# 05_FMC_HPC1.net
KiCad netlist of a schematic drawn in Altium Designer
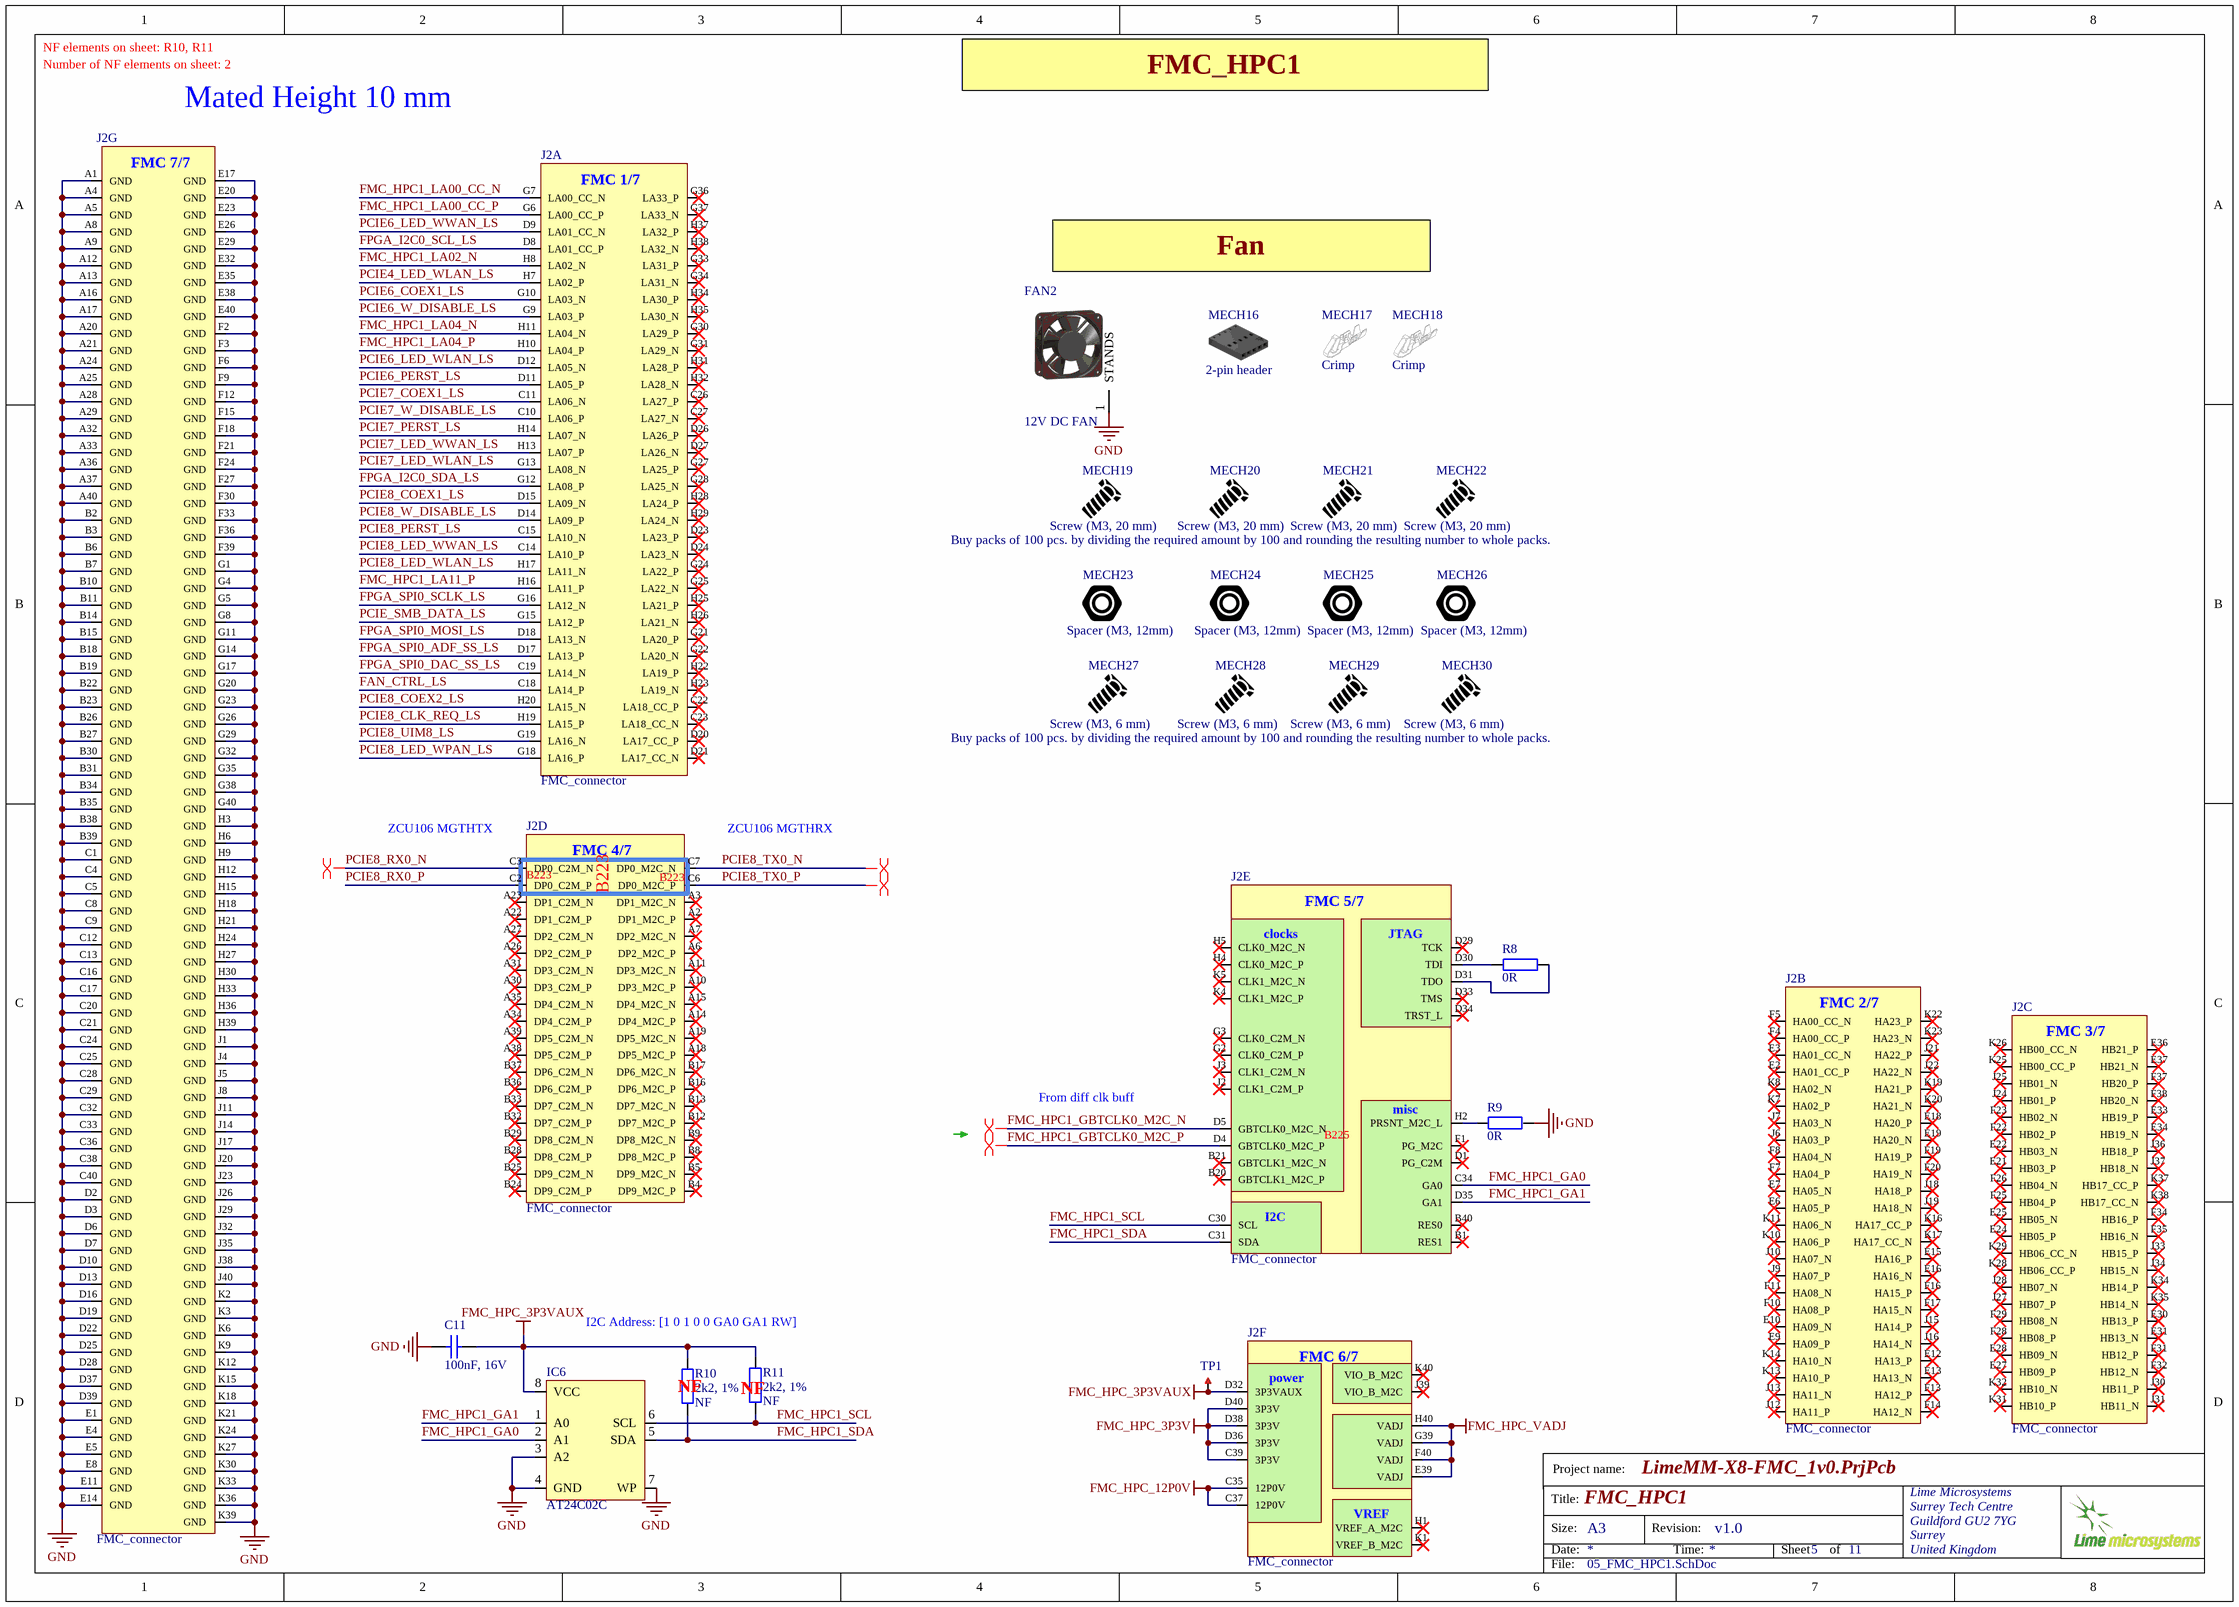
[diagram p0: 05_FMC_HPC1.SchDoc]

(export (version "E")
  (design (tool "Eeschema 10.0.6"))
  (components
    (comp (ref "C11")
      (value "100nF, 16V")
      (footprint "CAP0402")
      (fields (field (name "TOLERANCE") "10 %") (field (name "MANUFACTURER") "Murata Electronics"))
      (libsource (lib "LimeFPGAboard_schLib") (part "Cap_0603"))
    )
    (comp (ref "FAN2")
      (value "12V DC FAN")
      (footprint "FAN_80mm")
      (fields (field (name "MANUFACTURER") "Sunon"))
      (libsource (lib "LimeMicroAltiumLib_schLib_r04") (part "12V_DC_FAN"))
    )
    (comp (ref "IC6")
      (value "AT24C02C")
      (footprint "SOIC127P600-8DL_v2")
      (fields (field (name "MANUFACTURER") "ATMEL"))
      (libsource (lib "LimeMicroAltiumLib_schLib") (part "AT24C02C-SSHM-B"))
    )
    (comp (ref "J2")
      (value "FMC_connector")
      (footprint "FMC_HPC_terminal_conn_ASP-134488-01")
      (fields (field (name "MANUFACTURER") "Samtec"))
      (libsource (lib "LimeMicroAltiumLib") (part "FMC_connector"))
    )
    (comp (ref "MECH16")
      (value "2-pin header")
      (fields (field (name "MANUFACTURER") "Molex"))
      (libsource (lib "LimeMicroAltiumLib_schLib_r05") (part "Universal_crimped_header"))
    )
    (comp (ref "MECH17")
      (value "Crimp")
      (fields (field (name "MANUFACTURER") "Molex"))
      (libsource (lib "LimeMicroAltiumLib_schLib_r05") (part "Universal_crimp"))
    )
    (comp (ref "MECH18")
      (value "Crimp")
      (fields (field (name "MANUFACTURER") "Molex"))
      (libsource (lib "LimeMicroAltiumLib_schLib_r05") (part "Universal_crimp"))
    )
    (comp (ref "MECH19")
      (value "Screw (M3, 20 mm)")
      (fields (field (name "MANUFACTURER") "TR Fastenings"))
      (libsource (lib "LimeMicroAltiumLib_schLib_r05") (part "Universal_mech_screw"))
    )
    (comp (ref "MECH20")
      (value "Screw (M3, 20 mm)")
      (fields
        (field (name "ASSEMBLY INFO") "Buy packs of 100 pcs. by dividing the required amount by 100 and rounding the resulting number to whole packs.")
        (field (name "MANUFACTURER") "TR Fastenings")
      )
      (libsource (lib "LimeMicroAltiumLib_schLib_r05") (part "Universal_mech_screw"))
    )
    (comp (ref "MECH21")
      (value "Screw (M3, 20 mm)")
      (fields (field (name "MANUFACTURER") "TR Fastenings"))
      (libsource (lib "LimeMicroAltiumLib_schLib_r05") (part "Universal_mech_screw"))
    )
    (comp (ref "MECH22")
      (value "Screw (M3, 20 mm)")
      (fields (field (name "MANUFACTURER") "TR Fastenings"))
      (libsource (lib "LimeMicroAltiumLib_schLib_r05") (part "Universal_mech_screw"))
    )
    (comp (ref "MECH23")
      (value "Spacer (M3, 12mm)")
      (fields (field (name "MANUFACTURER") "ETTINGER"))
      (libsource (lib "LimeMicroAltiumLib_schLib_r05") (part "Universal_mech_nut"))
    )
    (comp (ref "MECH24")
      (value "Spacer (M3, 12mm)")
      (fields (field (name "MANUFACTURER") "ETTINGER"))
      (libsource (lib "LimeMicroAltiumLib_schLib_r05") (part "Universal_mech_nut"))
    )
    (comp (ref "MECH25")
      (value "Spacer (M3, 12mm)")
      (fields (field (name "MANUFACTURER") "ETTINGER"))
      (libsource (lib "LimeMicroAltiumLib_schLib_r05") (part "Universal_mech_nut"))
    )
    (comp (ref "MECH26")
      (value "Spacer (M3, 12mm)")
      (fields (field (name "MANUFACTURER") "ETTINGER"))
      (libsource (lib "LimeMicroAltiumLib_schLib_r05") (part "Universal_mech_nut"))
    )
    (comp (ref "MECH27")
      (value "Screw (M3, 6 mm)")
      (fields (field (name "MANUFACTURER") "TR Fastenings"))
      (libsource (lib "LimeMicroAltiumLib_schLib_r05") (part "Universal_mech_screw"))
    )
    (comp (ref "MECH28")
      (value "Screw (M3, 6 mm)")
      (fields
        (field (name "ASSEMBLY INFO") "Buy packs of 100 pcs. by dividing the required amount by 100 and rounding the resulting number to whole packs.")
        (field (name "MANUFACTURER") "TR Fastenings")
      )
      (libsource (lib "LimeMicroAltiumLib_schLib_r05") (part "Universal_mech_screw"))
    )
    (comp (ref "MECH29")
      (value "Screw (M3, 6 mm)")
      (fields (field (name "MANUFACTURER") "TR Fastenings"))
      (libsource (lib "LimeMicroAltiumLib_schLib_r05") (part "Universal_mech_screw"))
    )
    (comp (ref "MECH30")
      (value "Screw (M3, 6 mm)")
      (fields (field (name "MANUFACTURER") "TR Fastenings"))
      (libsource (lib "LimeMicroAltiumLib_schLib_r05") (part "Universal_mech_screw"))
    )
    (comp (ref "R8")
      (value "0R")
      (footprint "RES0402")
      (fields (field (name "MANUFACTURER") "Yageo") (field (name "TOLERANCE") "Jumper"))
      (libsource (lib "") (part "Res_0402_1"))
    )
    (comp (ref "R9")
      (value "0R")
      (footprint "RES0402")
      (fields (field (name "MANUFACTURER") "Yageo") (field (name "TOLERANCE") "Jumper"))
      (libsource (lib "LimeMicroAltiumLib_schLib") (part "Res_0402"))
    )
    (comp (ref "R10")
      (value "2k2, 1%")
      (footprint "RES0402")
      (fields
        (field (name "ASSEMBLY INFO") "NF")
        (field (name "MANUFACTURER") "Stackpole Electronics Inc")
        (field (name "TOLERANCE") "±1%")
      )
      (libsource (lib "") (part "Res_0402_1"))
    )
    (comp (ref "R11")
      (value "2k2, 1%")
      (footprint "RES0402")
      (fields
        (field (name "ASSEMBLY INFO") "NF")
        (field (name "MANUFACTURER") "Stackpole Electronics Inc")
        (field (name "TOLERANCE") "±1%")
      )
      (libsource (lib "") (part "Res_0402_1"))
    )
    (comp (ref "TP1")
      (value "TESTPOINT_PAD")
      (footprint "TP_PAD_1p5MM")
      (description "Test Point PCB mount Miniature White")
      (libsource (lib "LimeMicroAltiumLib_schLib_r04") (part "TESTPOINT_PAD"))
    )
  )
  (nets
    (net (code "1") (name "/FAN_CTRL_LS") (class "Default")
      (node (ref "J2") (pin "C18") (pinfunction "LA14_P_C18") (pintype "passive"))
    )
    (net (code "2") (name "/FMC_HPC1_GA0") (class "Default")
      (node (ref "IC6") (pin "2") (pinfunction "A1_2") (pintype "passive"))
      (node (ref "J2") (pin "C34") (pinfunction "GA0_C34") (pintype "passive"))
    )
    (net (code "3") (name "/FMC_HPC1_GA1") (class "Default")
      (node (ref "IC6") (pin "1") (pinfunction "A0_1") (pintype "passive"))
      (node (ref "J2") (pin "D35") (pinfunction "GA1_D35") (pintype "passive"))
    )
    (net (code "4") (name "/FMC_HPC1_GBTCLK0_M2C_N") (class "Default")
      (node (ref "J2") (pin "D5") (pinfunction "GBTCLK0_M2C_N_D5") (pintype "passive"))
    )
    (net (code "5") (name "/FMC_HPC1_GBTCLK0_M2C_P") (class "Default")
      (node (ref "J2") (pin "D4") (pinfunction "GBTCLK0_M2C_P_D4") (pintype "passive"))
    )
    (net (code "6") (name "/FMC_HPC1_LA00_CC_N") (class "Default")
      (node (ref "J2") (pin "G7") (pinfunction "LA00_CC_N_G7") (pintype "passive"))
    )
    (net (code "7") (name "/FMC_HPC1_LA00_CC_P") (class "Default")
      (node (ref "J2") (pin "G6") (pinfunction "LA00_CC_P_G6") (pintype "passive"))
    )
    (net (code "8") (name "/FMC_HPC1_LA02_N") (class "Default")
      (node (ref "J2") (pin "H8") (pinfunction "LA02_N_H8") (pintype "passive"))
    )
    (net (code "9") (name "/FMC_HPC1_LA04_N") (class "Default")
      (node (ref "J2") (pin "H11") (pinfunction "LA04_N_H11") (pintype "passive"))
    )
    (net (code "10") (name "/FMC_HPC1_LA04_P") (class "Default")
      (node (ref "J2") (pin "H10") (pinfunction "LA04_P_H10") (pintype "passive"))
    )
    (net (code "11") (name "/FMC_HPC1_LA11_P") (class "Default")
      (node (ref "J2") (pin "H16") (pinfunction "LA11_P_H16") (pintype "passive"))
    )
    (net (code "12") (name "/FMC_HPC1_SCL") (class "Default")
      (node (ref "IC6") (pin "6") (pinfunction "SCL_6") (pintype "passive"))
      (node (ref "J2") (pin "C30") (pinfunction "SCL_C30") (pintype "passive"))
      (node (ref "R11") (pin "2") (pinfunction "2_2") (pintype "passive"))
    )
    (net (code "13") (name "/FMC_HPC1_SDA") (class "Default")
      (node (ref "IC6") (pin "5") (pinfunction "SDA_5") (pintype "passive"))
      (node (ref "J2") (pin "C31") (pinfunction "SDA_C31") (pintype "passive"))
      (node (ref "R10") (pin "2") (pinfunction "2_2") (pintype "passive"))
    )
    (net (code "14") (name "/FPGA_I2C0_SCL_LS") (class "Default")
      (node (ref "J2") (pin "D8") (pinfunction "LA01_CC_P_D8") (pintype "passive"))
    )
    (net (code "15") (name "/FPGA_I2C0_SDA_LS") (class "Default")
      (node (ref "J2") (pin "G12") (pinfunction "LA08_P_G12") (pintype "passive"))
    )
    (net (code "16") (name "/FPGA_SPI0_ADF_SS_LS") (class "Default")
      (node (ref "J2") (pin "D17") (pinfunction "LA13_P_D17") (pintype "passive"))
    )
    (net (code "17") (name "/FPGA_SPI0_DAC_SS_LS") (class "Default")
      (node (ref "J2") (pin "C19") (pinfunction "LA14_N_C19") (pintype "passive"))
    )
    (net (code "18") (name "/FPGA_SPI0_MOSI_LS") (class "Default")
      (node (ref "J2") (pin "D18") (pinfunction "LA13_N_D18") (pintype "passive"))
    )
    (net (code "19") (name "/FPGA_SPI0_SCLK_LS") (class "Default")
      (node (ref "J2") (pin "G16") (pinfunction "LA12_N_G16") (pintype "passive"))
    )
    (net (code "20") (name "/PCIE4_LED_WLAN_LS") (class "Default")
      (node (ref "J2") (pin "H7") (pinfunction "LA02_P_H7") (pintype "passive"))
    )
    (net (code "21") (name "/PCIE6_COEX1_LS") (class "Default")
      (node (ref "J2") (pin "G10") (pinfunction "LA03_N_G10") (pintype "passive"))
    )
    (net (code "22") (name "/PCIE6_LED_WLAN_LS") (class "Default")
      (node (ref "J2") (pin "D12") (pinfunction "LA05_N_D12") (pintype "passive"))
    )
    (net (code "23") (name "/PCIE6_LED_WWAN_LS") (class "Default")
      (node (ref "J2") (pin "D9") (pinfunction "LA01_CC_N_D9") (pintype "passive"))
    )
    (net (code "24") (name "/PCIE6_PERST_LS") (class "Default")
      (node (ref "J2") (pin "D11") (pinfunction "LA05_P_D11") (pintype "passive"))
    )
    (net (code "25") (name "/PCIE6_W_DISABLE_LS") (class "Default")
      (node (ref "J2") (pin "G9") (pinfunction "LA03_P_G9") (pintype "passive"))
    )
    (net (code "26") (name "/PCIE7_COEX1_LS") (class "Default")
      (node (ref "J2") (pin "C11") (pinfunction "LA06_N_C11") (pintype "passive"))
    )
    (net (code "27") (name "/PCIE7_LED_WLAN_LS") (class "Default")
      (node (ref "J2") (pin "G13") (pinfunction "LA08_N_G13") (pintype "passive"))
    )
    (net (code "28") (name "/PCIE7_LED_WWAN_LS") (class "Default")
      (node (ref "J2") (pin "H13") (pinfunction "LA07_P_H13") (pintype "passive"))
    )
    (net (code "29") (name "/PCIE7_PERST_LS") (class "Default")
      (node (ref "J2") (pin "H14") (pinfunction "LA07_N_H14") (pintype "passive"))
    )
    (net (code "30") (name "/PCIE7_W_DISABLE_LS") (class "Default")
      (node (ref "J2") (pin "C10") (pinfunction "LA06_P_C10") (pintype "passive"))
    )
    (net (code "31") (name "/PCIE8_CLK_REQ_LS") (class "Default")
      (node (ref "J2") (pin "H19") (pinfunction "LA15_P_H19") (pintype "passive"))
    )
    (net (code "32") (name "/PCIE8_COEX1_LS") (class "Default")
      (node (ref "J2") (pin "D15") (pinfunction "LA09_N_D15") (pintype "passive"))
    )
    (net (code "33") (name "/PCIE8_COEX2_LS") (class "Default")
      (node (ref "J2") (pin "H20") (pinfunction "LA15_N_H20") (pintype "passive"))
    )
    (net (code "34") (name "/PCIE8_LED_WLAN_LS") (class "Default")
      (node (ref "J2") (pin "H17") (pinfunction "LA11_N_H17") (pintype "passive"))
    )
    (net (code "35") (name "/PCIE8_LED_WPAN_LS") (class "Default")
      (node (ref "J2") (pin "G18") (pinfunction "LA16_P_G18") (pintype "passive"))
    )
    (net (code "36") (name "/PCIE8_LED_WWAN_LS") (class "Default")
      (node (ref "J2") (pin "C14") (pinfunction "LA10_P_C14") (pintype "passive"))
    )
    (net (code "37") (name "/PCIE8_PERST_LS") (class "Default")
      (node (ref "J2") (pin "C15") (pinfunction "LA10_N_C15") (pintype "passive"))
    )
    (net (code "38") (name "/PCIE8_RX0_N") (class "Default")
      (node (ref "J2") (pin "C3") (pinfunction "DP0_C2M_N_C3") (pintype "passive"))
    )
    (net (code "39") (name "/PCIE8_RX0_P") (class "Default")
      (node (ref "J2") (pin "C2") (pinfunction "DP0_C2M_P_C2") (pintype "passive"))
    )
    (net (code "40") (name "/PCIE8_TX0_N") (class "Default")
      (node (ref "J2") (pin "C7") (pinfunction "DP0_M2C_N_C7") (pintype "passive"))
    )
    (net (code "41") (name "/PCIE8_TX0_P") (class "Default")
      (node (ref "J2") (pin "C6") (pinfunction "DP0_M2C_P_C6") (pintype "passive"))
    )
    (net (code "42") (name "/PCIE8_UIM8_LS") (class "Default")
      (node (ref "J2") (pin "G19") (pinfunction "LA16_N_G19") (pintype "passive"))
    )
    (net (code "43") (name "/PCIE8_W_DISABLE_LS") (class "Default")
      (node (ref "J2") (pin "D14") (pinfunction "LA09_P_D14") (pintype "passive"))
    )
    (net (code "44") (name "/PCIE_SMB_DATA_LS") (class "Default")
      (node (ref "J2") (pin "G15") (pinfunction "LA12_P_G15") (pintype "passive"))
    )
    (net (code "45") (name "FMC_HPC_3P3V") (class "Default")
      (node (ref "J2") (pin "C39") (pinfunction "3P3V_C39") (pintype "passive"))
      (node (ref "J2") (pin "D36") (pinfunction "3P3V_D36") (pintype "passive"))
      (node (ref "J2") (pin "D38") (pinfunction "3P3V_D38") (pintype "passive"))
      (node (ref "J2") (pin "D40") (pinfunction "3P3V_D40") (pintype "passive"))
    )
    (net (code "46") (name "FMC_HPC_3P3VAUX") (class "Default")
      (node (ref "C11") (pin "1") (pinfunction "1_1") (pintype "passive"))
      (node (ref "IC6") (pin "8") (pinfunction "VCC_8") (pintype "passive"))
      (node (ref "J2") (pin "D32") (pinfunction "3P3VAUX_D32") (pintype "passive"))
      (node (ref "R10") (pin "1") (pinfunction "1_1") (pintype "passive"))
      (node (ref "R11") (pin "1") (pinfunction "1_1") (pintype "passive"))
      (node (ref "TP1") (pin "1") (pintype "passive"))
    )
    (net (code "47") (name "FMC_HPC_12P0V") (class "Default")
      (node (ref "J2") (pin "C35") (pinfunction "12P0V_C35") (pintype "passive"))
      (node (ref "J2") (pin "C37") (pinfunction "12P0V_C37") (pintype "passive"))
    )
    (net (code "48") (name "FMC_HPC_VADJ") (class "Default")
      (node (ref "J2") (pin "E39") (pinfunction "VADJ_E39") (pintype "passive"))
      (node (ref "J2") (pin "F40") (pinfunction "VADJ_F40") (pintype "passive"))
      (node (ref "J2") (pin "G39") (pinfunction "VADJ_G39") (pintype "passive"))
      (node (ref "J2") (pin "H40") (pinfunction "VADJ_H40") (pintype "passive"))
    )
    (net (code "49") (name "GND") (class "Default")
      (node (ref "C11") (pin "2") (pinfunction "2_2") (pintype "passive"))
      (node (ref "FAN2") (pin "1") (pinfunction "STANDS_1") (pintype "passive"))
      (node (ref "IC6") (pin "3") (pinfunction "A2_3") (pintype "passive"))
      (node (ref "IC6") (pin "4") (pinfunction "GND_4") (pintype "passive"))
      (node (ref "IC6") (pin "7") (pinfunction "WP_7") (pintype "passive"))
      (node (ref "J2") (pin "A1") (pinfunction "GND_A1") (pintype "passive"))
      (node (ref "J2") (pin "A12") (pinfunction "GND_A12") (pintype "passive"))
      (node (ref "J2") (pin "A13") (pinfunction "GND_A13") (pintype "passive"))
      (node (ref "J2") (pin "A16") (pinfunction "GND_A16") (pintype "passive"))
      (node (ref "J2") (pin "A17") (pinfunction "GND_A17") (pintype "passive"))
      (node (ref "J2") (pin "A20") (pinfunction "GND_A20") (pintype "passive"))
      (node (ref "J2") (pin "A21") (pinfunction "GND_A21") (pintype "passive"))
      (node (ref "J2") (pin "A24") (pinfunction "GND_A24") (pintype "passive"))
      (node (ref "J2") (pin "A25") (pinfunction "GND_A25") (pintype "passive"))
      (node (ref "J2") (pin "A28") (pinfunction "GND_A28") (pintype "passive"))
      (node (ref "J2") (pin "A29") (pinfunction "GND_A29") (pintype "passive"))
      (node (ref "J2") (pin "A32") (pinfunction "GND_A32") (pintype "passive"))
      (node (ref "J2") (pin "A33") (pinfunction "GND_A33") (pintype "passive"))
      (node (ref "J2") (pin "A36") (pinfunction "GND_A36") (pintype "passive"))
      (node (ref "J2") (pin "A37") (pinfunction "GND_A37") (pintype "passive"))
      (node (ref "J2") (pin "A4") (pinfunction "GND_A4") (pintype "passive"))
      (node (ref "J2") (pin "A40") (pinfunction "GND_A40") (pintype "passive"))
      (node (ref "J2") (pin "A5") (pinfunction "GND_A5") (pintype "passive"))
      (node (ref "J2") (pin "A8") (pinfunction "GND_A8") (pintype "passive"))
      (node (ref "J2") (pin "A9") (pinfunction "GND_A9") (pintype "passive"))
      (node (ref "J2") (pin "B10") (pinfunction "GND_B10") (pintype "passive"))
      (node (ref "J2") (pin "B11") (pinfunction "GND_B11") (pintype "passive"))
      (node (ref "J2") (pin "B14") (pinfunction "GND_B14") (pintype "passive"))
      (node (ref "J2") (pin "B15") (pinfunction "GND_B15") (pintype "passive"))
      (node (ref "J2") (pin "B18") (pinfunction "GND_B18") (pintype "passive"))
      (node (ref "J2") (pin "B19") (pinfunction "GND_B19") (pintype "passive"))
      (node (ref "J2") (pin "B2") (pinfunction "GND_B2") (pintype "passive"))
      (node (ref "J2") (pin "B22") (pinfunction "GND_B22") (pintype "passive"))
      (node (ref "J2") (pin "B23") (pinfunction "GND_B23") (pintype "passive"))
      (node (ref "J2") (pin "B26") (pinfunction "GND_B26") (pintype "passive"))
      (node (ref "J2") (pin "B27") (pinfunction "GND_B27") (pintype "passive"))
      (node (ref "J2") (pin "B3") (pinfunction "GND_B3") (pintype "passive"))
      (node (ref "J2") (pin "B30") (pinfunction "GND_B30") (pintype "passive"))
      (node (ref "J2") (pin "B31") (pinfunction "GND_B31") (pintype "passive"))
      (node (ref "J2") (pin "B34") (pinfunction "GND_B34") (pintype "passive"))
      (node (ref "J2") (pin "B35") (pinfunction "GND_B35") (pintype "passive"))
      (node (ref "J2") (pin "B38") (pinfunction "GND_B38") (pintype "passive"))
      (node (ref "J2") (pin "B39") (pinfunction "GND_B39") (pintype "passive"))
      (node (ref "J2") (pin "B6") (pinfunction "GND_B6") (pintype "passive"))
      (node (ref "J2") (pin "B7") (pinfunction "GND_B7") (pintype "passive"))
      (node (ref "J2") (pin "C1") (pinfunction "GND_C1") (pintype "passive"))
      (node (ref "J2") (pin "C12") (pinfunction "GND_C12") (pintype "passive"))
      (node (ref "J2") (pin "C13") (pinfunction "GND_C13") (pintype "passive"))
      (node (ref "J2") (pin "C16") (pinfunction "GND_C16") (pintype "passive"))
      (node (ref "J2") (pin "C17") (pinfunction "GND_C17") (pintype "passive"))
      (node (ref "J2") (pin "C20") (pinfunction "GND_C20") (pintype "passive"))
      (node (ref "J2") (pin "C21") (pinfunction "GND_C21") (pintype "passive"))
      (node (ref "J2") (pin "C24") (pinfunction "GND_C24") (pintype "passive"))
      (node (ref "J2") (pin "C25") (pinfunction "GND_C25") (pintype "passive"))
      (node (ref "J2") (pin "C28") (pinfunction "GND_C28") (pintype "passive"))
      (node (ref "J2") (pin "C29") (pinfunction "GND_C29") (pintype "passive"))
      (node (ref "J2") (pin "C32") (pinfunction "GND_C32") (pintype "passive"))
      (node (ref "J2") (pin "C33") (pinfunction "GND_C33") (pintype "passive"))
      (node (ref "J2") (pin "C36") (pinfunction "GND_C36") (pintype "passive"))
      (node (ref "J2") (pin "C38") (pinfunction "GND_C38") (pintype "passive"))
      (node (ref "J2") (pin "C4") (pinfunction "GND_C4") (pintype "passive"))
      (node (ref "J2") (pin "C40") (pinfunction "GND_C40") (pintype "passive"))
      (node (ref "J2") (pin "C5") (pinfunction "GND_C5") (pintype "passive"))
      (node (ref "J2") (pin "C8") (pinfunction "GND_C8") (pintype "passive"))
      (node (ref "J2") (pin "C9") (pinfunction "GND_C9") (pintype "passive"))
      (node (ref "J2") (pin "D10") (pinfunction "GND_D10") (pintype "passive"))
      (node (ref "J2") (pin "D13") (pinfunction "GND_D13") (pintype "passive"))
      (node (ref "J2") (pin "D16") (pinfunction "GND_D16") (pintype "passive"))
      (node (ref "J2") (pin "D19") (pinfunction "GND_D19") (pintype "passive"))
      (node (ref "J2") (pin "D2") (pinfunction "GND_D2") (pintype "passive"))
      (node (ref "J2") (pin "D22") (pinfunction "GND_D22") (pintype "passive"))
      (node (ref "J2") (pin "D25") (pinfunction "GND_D25") (pintype "passive"))
      (node (ref "J2") (pin "D28") (pinfunction "GND_D28") (pintype "passive"))
      (node (ref "J2") (pin "D3") (pinfunction "GND_D3") (pintype "passive"))
      (node (ref "J2") (pin "D37") (pinfunction "GND_D37") (pintype "passive"))
      (node (ref "J2") (pin "D39") (pinfunction "GND_D39") (pintype "passive"))
      (node (ref "J2") (pin "D6") (pinfunction "GND_D6") (pintype "passive"))
      (node (ref "J2") (pin "D7") (pinfunction "GND_D7") (pintype "passive"))
      (node (ref "J2") (pin "E1") (pinfunction "GND_E1") (pintype "passive"))
      (node (ref "J2") (pin "E11") (pinfunction "GND_E11") (pintype "passive"))
      (node (ref "J2") (pin "E14") (pinfunction "GND_E14") (pintype "passive"))
      (node (ref "J2") (pin "E17") (pinfunction "GND_E17") (pintype "passive"))
      (node (ref "J2") (pin "E20") (pinfunction "GND_E20") (pintype "passive"))
      (node (ref "J2") (pin "E23") (pinfunction "GND_E23") (pintype "passive"))
      (node (ref "J2") (pin "E26") (pinfunction "GND_E26") (pintype "passive"))
      (node (ref "J2") (pin "E29") (pinfunction "GND_E29") (pintype "passive"))
      (node (ref "J2") (pin "E32") (pinfunction "GND_E32") (pintype "passive"))
      (node (ref "J2") (pin "E35") (pinfunction "GND_E35") (pintype "passive"))
      (node (ref "J2") (pin "E38") (pinfunction "GND_E38") (pintype "passive"))
      (node (ref "J2") (pin "E4") (pinfunction "GND_E4") (pintype "passive"))
      (node (ref "J2") (pin "E40") (pinfunction "GND_E40") (pintype "passive"))
      (node (ref "J2") (pin "E5") (pinfunction "GND_E5") (pintype "passive"))
      (node (ref "J2") (pin "E8") (pinfunction "GND_E8") (pintype "passive"))
      (node (ref "J2") (pin "F12") (pinfunction "GND_F12") (pintype "passive"))
      (node (ref "J2") (pin "F15") (pinfunction "GND_F15") (pintype "passive"))
      (node (ref "J2") (pin "F18") (pinfunction "GND_F18") (pintype "passive"))
      (node (ref "J2") (pin "F2") (pinfunction "GND_F2") (pintype "passive"))
      (node (ref "J2") (pin "F21") (pinfunction "GND_F21") (pintype "passive"))
      (node (ref "J2") (pin "F24") (pinfunction "GND_F24") (pintype "passive"))
      (node (ref "J2") (pin "F27") (pinfunction "GND_F27") (pintype "passive"))
      (node (ref "J2") (pin "F3") (pinfunction "GND_F3") (pintype "passive"))
      (node (ref "J2") (pin "F30") (pinfunction "GND_F30") (pintype "passive"))
      (node (ref "J2") (pin "F33") (pinfunction "GND_F33") (pintype "passive"))
      (node (ref "J2") (pin "F36") (pinfunction "GND_F36") (pintype "passive"))
      (node (ref "J2") (pin "F39") (pinfunction "GND_F39") (pintype "passive"))
      (node (ref "J2") (pin "F6") (pinfunction "GND_F6") (pintype "passive"))
      (node (ref "J2") (pin "F9") (pinfunction "GND_F9") (pintype "passive"))
      (node (ref "J2") (pin "G1") (pinfunction "GND_G1") (pintype "passive"))
      (node (ref "J2") (pin "G11") (pinfunction "GND_G11") (pintype "passive"))
      (node (ref "J2") (pin "G14") (pinfunction "GND_G14") (pintype "passive"))
      (node (ref "J2") (pin "G17") (pinfunction "GND_G17") (pintype "passive"))
      (node (ref "J2") (pin "G20") (pinfunction "GND_G20") (pintype "passive"))
      (node (ref "J2") (pin "G23") (pinfunction "GND_G23") (pintype "passive"))
      (node (ref "J2") (pin "G26") (pinfunction "GND_G26") (pintype "passive"))
      (node (ref "J2") (pin "G29") (pinfunction "GND_G29") (pintype "passive"))
      (node (ref "J2") (pin "G32") (pinfunction "GND_G32") (pintype "passive"))
      (node (ref "J2") (pin "G35") (pinfunction "GND_G35") (pintype "passive"))
      (node (ref "J2") (pin "G38") (pinfunction "GND_G38") (pintype "passive"))
      (node (ref "J2") (pin "G4") (pinfunction "GND_G4") (pintype "passive"))
      (node (ref "J2") (pin "G40") (pinfunction "GND_G40") (pintype "passive"))
      (node (ref "J2") (pin "G5") (pinfunction "GND_G5") (pintype "passive"))
      (node (ref "J2") (pin "G8") (pinfunction "GND_G8") (pintype "passive"))
      (node (ref "J2") (pin "H12") (pinfunction "GND_H12") (pintype "passive"))
      (node (ref "J2") (pin "H15") (pinfunction "GND_H15") (pintype "passive"))
      (node (ref "J2") (pin "H18") (pinfunction "GND_H18") (pintype "passive"))
      (node (ref "J2") (pin "H21") (pinfunction "GND_H21") (pintype "passive"))
      (node (ref "J2") (pin "H24") (pinfunction "GND_H24") (pintype "passive"))
      (node (ref "J2") (pin "H27") (pinfunction "GND_H27") (pintype "passive"))
      (node (ref "J2") (pin "H3") (pinfunction "GND_H3") (pintype "passive"))
      (node (ref "J2") (pin "H30") (pinfunction "GND_H30") (pintype "passive"))
      (node (ref "J2") (pin "H33") (pinfunction "GND_H33") (pintype "passive"))
      (node (ref "J2") (pin "H36") (pinfunction "GND_H36") (pintype "passive"))
      (node (ref "J2") (pin "H39") (pinfunction "GND_H39") (pintype "passive"))
      (node (ref "J2") (pin "H6") (pinfunction "GND_H6") (pintype "passive"))
      (node (ref "J2") (pin "H9") (pinfunction "GND_H9") (pintype "passive"))
      (node (ref "J2") (pin "J1") (pinfunction "GND_J1") (pintype "passive"))
      (node (ref "J2") (pin "J11") (pinfunction "GND_J11") (pintype "passive"))
      (node (ref "J2") (pin "J14") (pinfunction "GND_J14") (pintype "passive"))
      (node (ref "J2") (pin "J17") (pinfunction "GND_J17") (pintype "passive"))
      (node (ref "J2") (pin "J20") (pinfunction "GND_J20") (pintype "passive"))
      (node (ref "J2") (pin "J23") (pinfunction "GND_J23") (pintype "passive"))
      (node (ref "J2") (pin "J26") (pinfunction "GND_J26") (pintype "passive"))
      (node (ref "J2") (pin "J29") (pinfunction "GND_J29") (pintype "passive"))
      (node (ref "J2") (pin "J32") (pinfunction "GND_J32") (pintype "passive"))
      (node (ref "J2") (pin "J35") (pinfunction "GND_J35") (pintype "passive"))
      (node (ref "J2") (pin "J38") (pinfunction "GND_J38") (pintype "passive"))
      (node (ref "J2") (pin "J4") (pinfunction "GND_J4") (pintype "passive"))
      (node (ref "J2") (pin "J40") (pinfunction "GND_J40") (pintype "passive"))
      (node (ref "J2") (pin "J5") (pinfunction "GND_J5") (pintype "passive"))
      (node (ref "J2") (pin "J8") (pinfunction "GND_J8") (pintype "passive"))
      (node (ref "J2") (pin "K12") (pinfunction "GND_K12") (pintype "passive"))
      (node (ref "J2") (pin "K15") (pinfunction "GND_K15") (pintype "passive"))
      (node (ref "J2") (pin "K18") (pinfunction "GND_K18") (pintype "passive"))
      (node (ref "J2") (pin "K2") (pinfunction "GND_K2") (pintype "passive"))
      (node (ref "J2") (pin "K21") (pinfunction "GND_K21") (pintype "passive"))
      (node (ref "J2") (pin "K24") (pinfunction "GND_K24") (pintype "passive"))
      (node (ref "J2") (pin "K27") (pinfunction "GND_K27") (pintype "passive"))
      (node (ref "J2") (pin "K3") (pinfunction "GND_K3") (pintype "passive"))
      (node (ref "J2") (pin "K30") (pinfunction "GND_K30") (pintype "passive"))
      (node (ref "J2") (pin "K33") (pinfunction "GND_K33") (pintype "passive"))
      (node (ref "J2") (pin "K36") (pinfunction "GND_K36") (pintype "passive"))
      (node (ref "J2") (pin "K39") (pinfunction "GND_K39") (pintype "passive"))
      (node (ref "J2") (pin "K6") (pinfunction "GND_K6") (pintype "passive"))
      (node (ref "J2") (pin "K9") (pinfunction "GND_K9") (pintype "passive"))
      (node (ref "R9") (pin "2") (pinfunction "2_2") (pintype "passive"))
    )
    (net (code "50") (name "Net-(J2E-PRSNT_M2C_L)") (class "Default")
      (node (ref "J2") (pin "H2") (pinfunction "PRSNT_M2C_L_H2") (pintype "passive"))
      (node (ref "R9") (pin "1") (pinfunction "1_1") (pintype "passive"))
    )
    (net (code "51") (name "Net-(J2E-TDI)") (class "Default")
      (node (ref "J2") (pin "D30") (pinfunction "TDI_D30") (pintype "passive"))
      (node (ref "R8") (pin "2") (pinfunction "2_2") (pintype "passive"))
    )
    (net (code "52") (name "Net-(J2E-TDO)") (class "Default")
      (node (ref "J2") (pin "D31") (pinfunction "TDO_D31") (pintype "passive"))
      (node (ref "R8") (pin "1") (pinfunction "1_1") (pintype "passive"))
    )
    (net (code "53") (name "unconnected-(J2A-LA17_CC_N-PadD21)") (class "Default")
      (node (ref "J2") (pin "D21") (pinfunction "LA17_CC_N_D21") (pintype "passive+no_connect"))
    )
    (net (code "54") (name "unconnected-(J2A-LA17_CC_P-PadD20)") (class "Default")
      (node (ref "J2") (pin "D20") (pinfunction "LA17_CC_P_D20") (pintype "passive+no_connect"))
    )
    (net (code "55") (name "unconnected-(J2A-LA18_CC_N-PadC23)") (class "Default")
      (node (ref "J2") (pin "C23") (pinfunction "LA18_CC_N_C23") (pintype "passive+no_connect"))
    )
    (net (code "56") (name "unconnected-(J2A-LA18_CC_P-PadC22)") (class "Default")
      (node (ref "J2") (pin "C22") (pinfunction "LA18_CC_P_C22") (pintype "passive+no_connect"))
    )
    (net (code "57") (name "unconnected-(J2A-LA19_N-PadH23)") (class "Default")
      (node (ref "J2") (pin "H23") (pinfunction "LA19_N_H23") (pintype "passive+no_connect"))
    )
    (net (code "58") (name "unconnected-(J2A-LA19_P-PadH22)") (class "Default")
      (node (ref "J2") (pin "H22") (pinfunction "LA19_P_H22") (pintype "passive+no_connect"))
    )
    (net (code "59") (name "unconnected-(J2A-LA20_N-PadG22)") (class "Default")
      (node (ref "J2") (pin "G22") (pinfunction "LA20_N_G22") (pintype "passive+no_connect"))
    )
    (net (code "60") (name "unconnected-(J2A-LA20_P-PadG21)") (class "Default")
      (node (ref "J2") (pin "G21") (pinfunction "LA20_P_G21") (pintype "passive+no_connect"))
    )
    (net (code "61") (name "unconnected-(J2A-LA21_N-PadH26)") (class "Default")
      (node (ref "J2") (pin "H26") (pinfunction "LA21_N_H26") (pintype "passive+no_connect"))
    )
    (net (code "62") (name "unconnected-(J2A-LA21_P-PadH25)") (class "Default")
      (node (ref "J2") (pin "H25") (pinfunction "LA21_P_H25") (pintype "passive+no_connect"))
    )
    (net (code "63") (name "unconnected-(J2A-LA22_N-PadG25)") (class "Default")
      (node (ref "J2") (pin "G25") (pinfunction "LA22_N_G25") (pintype "passive+no_connect"))
    )
    (net (code "64") (name "unconnected-(J2A-LA22_P-PadG24)") (class "Default")
      (node (ref "J2") (pin "G24") (pinfunction "LA22_P_G24") (pintype "passive+no_connect"))
    )
    (net (code "65") (name "unconnected-(J2A-LA23_N-PadD24)") (class "Default")
      (node (ref "J2") (pin "D24") (pinfunction "LA23_N_D24") (pintype "passive+no_connect"))
    )
    (net (code "66") (name "unconnected-(J2A-LA23_P-PadD23)") (class "Default")
      (node (ref "J2") (pin "D23") (pinfunction "LA23_P_D23") (pintype "passive+no_connect"))
    )
    (net (code "67") (name "unconnected-(J2A-LA24_N-PadH29)") (class "Default")
      (node (ref "J2") (pin "H29") (pinfunction "LA24_N_H29") (pintype "passive+no_connect"))
    )
    (net (code "68") (name "unconnected-(J2A-LA24_P-PadH28)") (class "Default")
      (node (ref "J2") (pin "H28") (pinfunction "LA24_P_H28") (pintype "passive+no_connect"))
    )
    (net (code "69") (name "unconnected-(J2A-LA25_N-PadG28)") (class "Default")
      (node (ref "J2") (pin "G28") (pinfunction "LA25_N_G28") (pintype "passive+no_connect"))
    )
    (net (code "70") (name "unconnected-(J2A-LA25_P-PadG27)") (class "Default")
      (node (ref "J2") (pin "G27") (pinfunction "LA25_P_G27") (pintype "passive+no_connect"))
    )
    (net (code "71") (name "unconnected-(J2A-LA26_N-PadD27)") (class "Default")
      (node (ref "J2") (pin "D27") (pinfunction "LA26_N_D27") (pintype "passive+no_connect"))
    )
    (net (code "72") (name "unconnected-(J2A-LA26_P-PadD26)") (class "Default")
      (node (ref "J2") (pin "D26") (pinfunction "LA26_P_D26") (pintype "passive+no_connect"))
    )
    (net (code "73") (name "unconnected-(J2A-LA27_N-PadC27)") (class "Default")
      (node (ref "J2") (pin "C27") (pinfunction "LA27_N_C27") (pintype "passive+no_connect"))
    )
    (net (code "74") (name "unconnected-(J2A-LA27_P-PadC26)") (class "Default")
      (node (ref "J2") (pin "C26") (pinfunction "LA27_P_C26") (pintype "passive+no_connect"))
    )
    (net (code "75") (name "unconnected-(J2A-LA28_N-PadH32)") (class "Default")
      (node (ref "J2") (pin "H32") (pinfunction "LA28_N_H32") (pintype "passive+no_connect"))
    )
    (net (code "76") (name "unconnected-(J2A-LA28_P-PadH31)") (class "Default")
      (node (ref "J2") (pin "H31") (pinfunction "LA28_P_H31") (pintype "passive+no_connect"))
    )
    (net (code "77") (name "unconnected-(J2A-LA29_N-PadG31)") (class "Default")
      (node (ref "J2") (pin "G31") (pinfunction "LA29_N_G31") (pintype "passive+no_connect"))
    )
    (net (code "78") (name "unconnected-(J2A-LA29_P-PadG30)") (class "Default")
      (node (ref "J2") (pin "G30") (pinfunction "LA29_P_G30") (pintype "passive+no_connect"))
    )
    (net (code "79") (name "unconnected-(J2A-LA30_N-PadH35)") (class "Default")
      (node (ref "J2") (pin "H35") (pinfunction "LA30_N_H35") (pintype "passive+no_connect"))
    )
    (net (code "80") (name "unconnected-(J2A-LA30_P-PadH34)") (class "Default")
      (node (ref "J2") (pin "H34") (pinfunction "LA30_P_H34") (pintype "passive+no_connect"))
    )
    (net (code "81") (name "unconnected-(J2A-LA31_N-PadG34)") (class "Default")
      (node (ref "J2") (pin "G34") (pinfunction "LA31_N_G34") (pintype "passive+no_connect"))
    )
    (net (code "82") (name "unconnected-(J2A-LA31_P-PadG33)") (class "Default")
      (node (ref "J2") (pin "G33") (pinfunction "LA31_P_G33") (pintype "passive+no_connect"))
    )
    (net (code "83") (name "unconnected-(J2A-LA32_N-PadH38)") (class "Default")
      (node (ref "J2") (pin "H38") (pinfunction "LA32_N_H38") (pintype "passive+no_connect"))
    )
    (net (code "84") (name "unconnected-(J2A-LA32_P-PadH37)") (class "Default")
      (node (ref "J2") (pin "H37") (pinfunction "LA32_P_H37") (pintype "passive+no_connect"))
    )
    (net (code "85") (name "unconnected-(J2A-LA33_N-PadG37)") (class "Default")
      (node (ref "J2") (pin "G37") (pinfunction "LA33_N_G37") (pintype "passive+no_connect"))
    )
    (net (code "86") (name "unconnected-(J2A-LA33_P-PadG36)") (class "Default")
      (node (ref "J2") (pin "G36") (pinfunction "LA33_P_G36") (pintype "passive+no_connect"))
    )
    (net (code "87") (name "unconnected-(J2B-HA00_CC_N-PadF5)") (class "Default")
      (node (ref "J2") (pin "F5") (pinfunction "HA00_CC_N_F5") (pintype "passive+no_connect"))
    )
    (net (code "88") (name "unconnected-(J2B-HA00_CC_P-PadF4)") (class "Default")
      (node (ref "J2") (pin "F4") (pinfunction "HA00_CC_P_F4") (pintype "passive+no_connect"))
    )
    (net (code "89") (name "unconnected-(J2B-HA01_CC_N-PadE3)") (class "Default")
      (node (ref "J2") (pin "E3") (pinfunction "HA01_CC_N_E3") (pintype "passive+no_connect"))
    )
    (net (code "90") (name "unconnected-(J2B-HA01_CC_P-PadE2)") (class "Default")
      (node (ref "J2") (pin "E2") (pinfunction "HA01_CC_P_E2") (pintype "passive+no_connect"))
    )
    (net (code "91") (name "unconnected-(J2B-HA02_N-PadK8)") (class "Default")
      (node (ref "J2") (pin "K8") (pinfunction "HA02_N_K8") (pintype "passive+no_connect"))
    )
    (net (code "92") (name "unconnected-(J2B-HA02_P-PadK7)") (class "Default")
      (node (ref "J2") (pin "K7") (pinfunction "HA02_P_K7") (pintype "passive+no_connect"))
    )
    (net (code "93") (name "unconnected-(J2B-HA03_N-PadJ7)") (class "Default")
      (node (ref "J2") (pin "J7") (pinfunction "HA03_N_J7") (pintype "passive+no_connect"))
    )
    (net (code "94") (name "unconnected-(J2B-HA03_P-PadJ6)") (class "Default")
      (node (ref "J2") (pin "J6") (pinfunction "HA03_P_J6") (pintype "passive+no_connect"))
    )
    (net (code "95") (name "unconnected-(J2B-HA04_N-PadF8)") (class "Default")
      (node (ref "J2") (pin "F8") (pinfunction "HA04_N_F8") (pintype "passive+no_connect"))
    )
    (net (code "96") (name "unconnected-(J2B-HA04_P-PadF7)") (class "Default")
      (node (ref "J2") (pin "F7") (pinfunction "HA04_P_F7") (pintype "passive+no_connect"))
    )
    (net (code "97") (name "unconnected-(J2B-HA05_N-PadE7)") (class "Default")
      (node (ref "J2") (pin "E7") (pinfunction "HA05_N_E7") (pintype "passive+no_connect"))
    )
    (net (code "98") (name "unconnected-(J2B-HA05_P-PadE6)") (class "Default")
      (node (ref "J2") (pin "E6") (pinfunction "HA05_P_E6") (pintype "passive+no_connect"))
    )
    (net (code "99") (name "unconnected-(J2B-HA06_N-PadK11)") (class "Default")
      (node (ref "J2") (pin "K11") (pinfunction "HA06_N_K11") (pintype "passive+no_connect"))
    )
    (net (code "100") (name "unconnected-(J2B-HA06_P-PadK10)") (class "Default")
      (node (ref "J2") (pin "K10") (pinfunction "HA06_P_K10") (pintype "passive+no_connect"))
    )
    (net (code "101") (name "unconnected-(J2B-HA07_N-PadJ10)") (class "Default")
      (node (ref "J2") (pin "J10") (pinfunction "HA07_N_J10") (pintype "passive+no_connect"))
    )
    (net (code "102") (name "unconnected-(J2B-HA07_P-PadJ9)") (class "Default")
      (node (ref "J2") (pin "J9") (pinfunction "HA07_P_J9") (pintype "passive+no_connect"))
    )
    (net (code "103") (name "unconnected-(J2B-HA08_N-PadF11)") (class "Default")
      (node (ref "J2") (pin "F11") (pinfunction "HA08_N_F11") (pintype "passive+no_connect"))
    )
    (net (code "104") (name "unconnected-(J2B-HA08_P-PadF10)") (class "Default")
      (node (ref "J2") (pin "F10") (pinfunction "HA08_P_F10") (pintype "passive+no_connect"))
    )
    (net (code "105") (name "unconnected-(J2B-HA09_N-PadE10)") (class "Default")
      (node (ref "J2") (pin "E10") (pinfunction "HA09_N_E10") (pintype "passive+no_connect"))
    )
    (net (code "106") (name "unconnected-(J2B-HA09_P-PadE9)") (class "Default")
      (node (ref "J2") (pin "E9") (pinfunction "HA09_P_E9") (pintype "passive+no_connect"))
    )
    (net (code "107") (name "unconnected-(J2B-HA10_N-PadK14)") (class "Default")
      (node (ref "J2") (pin "K14") (pinfunction "HA10_N_K14") (pintype "passive+no_connect"))
    )
    (net (code "108") (name "unconnected-(J2B-HA10_P-PadK13)") (class "Default")
      (node (ref "J2") (pin "K13") (pinfunction "HA10_P_K13") (pintype "passive+no_connect"))
    )
    (net (code "109") (name "unconnected-(J2B-HA11_N-PadJ13)") (class "Default")
      (node (ref "J2") (pin "J13") (pinfunction "HA11_N_J13") (pintype "passive+no_connect"))
    )
    (net (code "110") (name "unconnected-(J2B-HA11_P-PadJ12)") (class "Default")
      (node (ref "J2") (pin "J12") (pinfunction "HA11_P_J12") (pintype "passive+no_connect"))
    )
    (net (code "111") (name "unconnected-(J2B-HA12_N-PadF14)") (class "Default")
      (node (ref "J2") (pin "F14") (pinfunction "HA12_N_F14") (pintype "passive+no_connect"))
    )
    (net (code "112") (name "unconnected-(J2B-HA12_P-PadF13)") (class "Default")
      (node (ref "J2") (pin "F13") (pinfunction "HA12_P_F13") (pintype "passive+no_connect"))
    )
    (net (code "113") (name "unconnected-(J2B-HA13_N-PadE13)") (class "Default")
      (node (ref "J2") (pin "E13") (pinfunction "HA13_N_E13") (pintype "passive+no_connect"))
    )
    (net (code "114") (name "unconnected-(J2B-HA13_P-PadE12)") (class "Default")
      (node (ref "J2") (pin "E12") (pinfunction "HA13_P_E12") (pintype "passive+no_connect"))
    )
    (net (code "115") (name "unconnected-(J2B-HA14_N-PadJ16)") (class "Default")
      (node (ref "J2") (pin "J16") (pinfunction "HA14_N_J16") (pintype "passive+no_connect"))
    )
    (net (code "116") (name "unconnected-(J2B-HA14_P-PadJ15)") (class "Default")
      (node (ref "J2") (pin "J15") (pinfunction "HA14_P_J15") (pintype "passive+no_connect"))
    )
    (net (code "117") (name "unconnected-(J2B-HA15_N-PadF17)") (class "Default")
      (node (ref "J2") (pin "F17") (pinfunction "HA15_N_F17") (pintype "passive+no_connect"))
    )
    (net (code "118") (name "unconnected-(J2B-HA15_P-PadF16)") (class "Default")
      (node (ref "J2") (pin "F16") (pinfunction "HA15_P_F16") (pintype "passive+no_connect"))
    )
    (net (code "119") (name "unconnected-(J2B-HA16_N-PadE16)") (class "Default")
      (node (ref "J2") (pin "E16") (pinfunction "HA16_N_E16") (pintype "passive+no_connect"))
    )
    (net (code "120") (name "unconnected-(J2B-HA16_P-PadE15)") (class "Default")
      (node (ref "J2") (pin "E15") (pinfunction "HA16_P_E15") (pintype "passive+no_connect"))
    )
    (net (code "121") (name "unconnected-(J2B-HA17_CC_N-PadK17)") (class "Default")
      (node (ref "J2") (pin "K17") (pinfunction "HA17_CC_N_K17") (pintype "passive+no_connect"))
    )
    (net (code "122") (name "unconnected-(J2B-HA17_CC_P-PadK16)") (class "Default")
      (node (ref "J2") (pin "K16") (pinfunction "HA17_CC_P_K16") (pintype "passive+no_connect"))
    )
    (net (code "123") (name "unconnected-(J2B-HA18_N-PadJ19)") (class "Default")
      (node (ref "J2") (pin "J19") (pinfunction "HA18_N_J19") (pintype "passive+no_connect"))
    )
    (net (code "124") (name "unconnected-(J2B-HA18_P-PadJ18)") (class "Default")
      (node (ref "J2") (pin "J18") (pinfunction "HA18_P_J18") (pintype "passive+no_connect"))
    )
    (net (code "125") (name "unconnected-(J2B-HA19_N-PadF20)") (class "Default")
      (node (ref "J2") (pin "F20") (pinfunction "HA19_N_F20") (pintype "passive+no_connect"))
    )
    (net (code "126") (name "unconnected-(J2B-HA19_P-PadF19)") (class "Default")
      (node (ref "J2") (pin "F19") (pinfunction "HA19_P_F19") (pintype "passive+no_connect"))
    )
    (net (code "127") (name "unconnected-(J2B-HA20_N-PadE19)") (class "Default")
      (node (ref "J2") (pin "E19") (pinfunction "HA20_N_E19") (pintype "passive+no_connect"))
    )
    (net (code "128") (name "unconnected-(J2B-HA20_P-PadE18)") (class "Default")
      (node (ref "J2") (pin "E18") (pinfunction "HA20_P_E18") (pintype "passive+no_connect"))
    )
    (net (code "129") (name "unconnected-(J2B-HA21_N-PadK20)") (class "Default")
      (node (ref "J2") (pin "K20") (pinfunction "HA21_N_K20") (pintype "passive+no_connect"))
    )
    (net (code "130") (name "unconnected-(J2B-HA21_P-PadK19)") (class "Default")
      (node (ref "J2") (pin "K19") (pinfunction "HA21_P_K19") (pintype "passive+no_connect"))
    )
    (net (code "131") (name "unconnected-(J2B-HA22_N-PadJ22)") (class "Default")
      (node (ref "J2") (pin "J22") (pinfunction "HA22_N_J22") (pintype "passive+no_connect"))
    )
    (net (code "132") (name "unconnected-(J2B-HA22_P-PadJ21)") (class "Default")
      (node (ref "J2") (pin "J21") (pinfunction "HA22_P_J21") (pintype "passive+no_connect"))
    )
    (net (code "133") (name "unconnected-(J2B-HA23_N-PadK23)") (class "Default")
      (node (ref "J2") (pin "K23") (pinfunction "HA23_N_K23") (pintype "passive+no_connect"))
    )
    (net (code "134") (name "unconnected-(J2B-HA23_P-PadK22)") (class "Default")
      (node (ref "J2") (pin "K22") (pinfunction "HA23_P_K22") (pintype "passive+no_connect"))
    )
    (net (code "135") (name "unconnected-(J2C-HB00_CC_N-PadK26)") (class "Default")
      (node (ref "J2") (pin "K26") (pinfunction "HB00_CC_N_K26") (pintype "passive+no_connect"))
    )
    (net (code "136") (name "unconnected-(J2C-HB00_CC_P-PadK25)") (class "Default")
      (node (ref "J2") (pin "K25") (pinfunction "HB00_CC_P_K25") (pintype "passive+no_connect"))
    )
    (net (code "137") (name "unconnected-(J2C-HB01_N-PadJ25)") (class "Default")
      (node (ref "J2") (pin "J25") (pinfunction "HB01_N_J25") (pintype "passive+no_connect"))
    )
    (net (code "138") (name "unconnected-(J2C-HB01_P-PadJ24)") (class "Default")
      (node (ref "J2") (pin "J24") (pinfunction "HB01_P_J24") (pintype "passive+no_connect"))
    )
    (net (code "139") (name "unconnected-(J2C-HB02_N-PadF23)") (class "Default")
      (node (ref "J2") (pin "F23") (pinfunction "HB02_N_F23") (pintype "passive+no_connect"))
    )
    (net (code "140") (name "unconnected-(J2C-HB02_P-PadF22)") (class "Default")
      (node (ref "J2") (pin "F22") (pinfunction "HB02_P_F22") (pintype "passive+no_connect"))
    )
    (net (code "141") (name "unconnected-(J2C-HB03_N-PadE22)") (class "Default")
      (node (ref "J2") (pin "E22") (pinfunction "HB03_N_E22") (pintype "passive+no_connect"))
    )
    (net (code "142") (name "unconnected-(J2C-HB03_P-PadE21)") (class "Default")
      (node (ref "J2") (pin "E21") (pinfunction "HB03_P_E21") (pintype "passive+no_connect"))
    )
    (net (code "143") (name "unconnected-(J2C-HB04_N-PadF26)") (class "Default")
      (node (ref "J2") (pin "F26") (pinfunction "HB04_N_F26") (pintype "passive+no_connect"))
    )
    (net (code "144") (name "unconnected-(J2C-HB04_P-PadF25)") (class "Default")
      (node (ref "J2") (pin "F25") (pinfunction "HB04_P_F25") (pintype "passive+no_connect"))
    )
    (net (code "145") (name "unconnected-(J2C-HB05_N-PadE25)") (class "Default")
      (node (ref "J2") (pin "E25") (pinfunction "HB05_N_E25") (pintype "passive+no_connect"))
    )
    (net (code "146") (name "unconnected-(J2C-HB05_P-PadE24)") (class "Default")
      (node (ref "J2") (pin "E24") (pinfunction "HB05_P_E24") (pintype "passive+no_connect"))
    )
    (net (code "147") (name "unconnected-(J2C-HB06_CC_N-PadK29)") (class "Default")
      (node (ref "J2") (pin "K29") (pinfunction "HB06_CC_N_K29") (pintype "passive+no_connect"))
    )
    (net (code "148") (name "unconnected-(J2C-HB06_CC_P-PadK28)") (class "Default")
      (node (ref "J2") (pin "K28") (pinfunction "HB06_CC_P_K28") (pintype "passive+no_connect"))
    )
    (net (code "149") (name "unconnected-(J2C-HB07_N-PadJ28)") (class "Default")
      (node (ref "J2") (pin "J28") (pinfunction "HB07_N_J28") (pintype "passive+no_connect"))
    )
    (net (code "150") (name "unconnected-(J2C-HB07_P-PadJ27)") (class "Default")
      (node (ref "J2") (pin "J27") (pinfunction "HB07_P_J27") (pintype "passive+no_connect"))
    )
    (net (code "151") (name "unconnected-(J2C-HB08_N-PadF29)") (class "Default")
      (node (ref "J2") (pin "F29") (pinfunction "HB08_N_F29") (pintype "passive+no_connect"))
    )
    (net (code "152") (name "unconnected-(J2C-HB08_P-PadF28)") (class "Default")
      (node (ref "J2") (pin "F28") (pinfunction "HB08_P_F28") (pintype "passive+no_connect"))
    )
    (net (code "153") (name "unconnected-(J2C-HB09_N-PadE28)") (class "Default")
      (node (ref "J2") (pin "E28") (pinfunction "HB09_N_E28") (pintype "passive+no_connect"))
    )
    (net (code "154") (name "unconnected-(J2C-HB09_P-PadE27)") (class "Default")
      (node (ref "J2") (pin "E27") (pinfunction "HB09_P_E27") (pintype "passive+no_connect"))
    )
    (net (code "155") (name "unconnected-(J2C-HB10_N-PadK32)") (class "Default")
      (node (ref "J2") (pin "K32") (pinfunction "HB10_N_K32") (pintype "passive+no_connect"))
    )
    (net (code "156") (name "unconnected-(J2C-HB10_P-PadK31)") (class "Default")
      (node (ref "J2") (pin "K31") (pinfunction "HB10_P_K31") (pintype "passive+no_connect"))
    )
    (net (code "157") (name "unconnected-(J2C-HB11_N-PadJ31)") (class "Default")
      (node (ref "J2") (pin "J31") (pinfunction "HB11_N_J31") (pintype "passive+no_connect"))
    )
    (net (code "158") (name "unconnected-(J2C-HB11_P-PadJ30)") (class "Default")
      (node (ref "J2") (pin "J30") (pinfunction "HB11_P_J30") (pintype "passive+no_connect"))
    )
    (net (code "159") (name "unconnected-(J2C-HB12_N-PadF32)") (class "Default")
      (node (ref "J2") (pin "F32") (pinfunction "HB12_N_F32") (pintype "passive+no_connect"))
    )
    (net (code "160") (name "unconnected-(J2C-HB12_P-PadF31)") (class "Default")
      (node (ref "J2") (pin "F31") (pinfunction "HB12_P_F31") (pintype "passive+no_connect"))
    )
    (net (code "161") (name "unconnected-(J2C-HB13_N-PadE31)") (class "Default")
      (node (ref "J2") (pin "E31") (pinfunction "HB13_N_E31") (pintype "passive+no_connect"))
    )
    (net (code "162") (name "unconnected-(J2C-HB13_P-PadE30)") (class "Default")
      (node (ref "J2") (pin "E30") (pinfunction "HB13_P_E30") (pintype "passive+no_connect"))
    )
    (net (code "163") (name "unconnected-(J2C-HB14_N-PadK35)") (class "Default")
      (node (ref "J2") (pin "K35") (pinfunction "HB14_N_K35") (pintype "passive+no_connect"))
    )
    (net (code "164") (name "unconnected-(J2C-HB14_P-PadK34)") (class "Default")
      (node (ref "J2") (pin "K34") (pinfunction "HB14_P_K34") (pintype "passive+no_connect"))
    )
    (net (code "165") (name "unconnected-(J2C-HB15_N-PadJ34)") (class "Default")
      (node (ref "J2") (pin "J34") (pinfunction "HB15_N_J34") (pintype "passive+no_connect"))
    )
    (net (code "166") (name "unconnected-(J2C-HB15_P-PadJ33)") (class "Default")
      (node (ref "J2") (pin "J33") (pinfunction "HB15_P_J33") (pintype "passive+no_connect"))
    )
    (net (code "167") (name "unconnected-(J2C-HB16_N-PadF35)") (class "Default")
      (node (ref "J2") (pin "F35") (pinfunction "HB16_N_F35") (pintype "passive+no_connect"))
    )
    (net (code "168") (name "unconnected-(J2C-HB16_P-PadF34)") (class "Default")
      (node (ref "J2") (pin "F34") (pinfunction "HB16_P_F34") (pintype "passive+no_connect"))
    )
    (net (code "169") (name "unconnected-(J2C-HB17_CC_N-PadK38)") (class "Default")
      (node (ref "J2") (pin "K38") (pinfunction "HB17_CC_N_K38") (pintype "passive+no_connect"))
    )
    (net (code "170") (name "unconnected-(J2C-HB17_CC_P-PadK37)") (class "Default")
      (node (ref "J2") (pin "K37") (pinfunction "HB17_CC_P_K37") (pintype "passive+no_connect"))
    )
    (net (code "171") (name "unconnected-(J2C-HB18_N-PadJ37)") (class "Default")
      (node (ref "J2") (pin "J37") (pinfunction "HB18_N_J37") (pintype "passive+no_connect"))
    )
    (net (code "172") (name "unconnected-(J2C-HB18_P-PadJ36)") (class "Default")
      (node (ref "J2") (pin "J36") (pinfunction "HB18_P_J36") (pintype "passive+no_connect"))
    )
    (net (code "173") (name "unconnected-(J2C-HB19_N-PadE34)") (class "Default")
      (node (ref "J2") (pin "E34") (pinfunction "HB19_N_E34") (pintype "passive+no_connect"))
    )
    (net (code "174") (name "unconnected-(J2C-HB19_P-PadE33)") (class "Default")
      (node (ref "J2") (pin "E33") (pinfunction "HB19_P_E33") (pintype "passive+no_connect"))
    )
    (net (code "175") (name "unconnected-(J2C-HB20_N-PadF38)") (class "Default")
      (node (ref "J2") (pin "F38") (pinfunction "HB20_N_F38") (pintype "passive+no_connect"))
    )
    (net (code "176") (name "unconnected-(J2C-HB20_P-PadF37)") (class "Default")
      (node (ref "J2") (pin "F37") (pinfunction "HB20_P_F37") (pintype "passive+no_connect"))
    )
    (net (code "177") (name "unconnected-(J2C-HB21_N-PadE37)") (class "Default")
      (node (ref "J2") (pin "E37") (pinfunction "HB21_N_E37") (pintype "passive+no_connect"))
    )
    (net (code "178") (name "unconnected-(J2C-HB21_P-PadE36)") (class "Default")
      (node (ref "J2") (pin "E36") (pinfunction "HB21_P_E36") (pintype "passive+no_connect"))
    )
    (net (code "179") (name "unconnected-(J2D-DP1_C2M_N-PadA23)") (class "Default")
      (node (ref "J2") (pin "A23") (pinfunction "DP1_C2M_N_A23") (pintype "passive+no_connect"))
    )
    (net (code "180") (name "unconnected-(J2D-DP1_C2M_P-PadA22)") (class "Default")
      (node (ref "J2") (pin "A22") (pinfunction "DP1_C2M_P_A22") (pintype "passive+no_connect"))
    )
    (net (code "181") (name "unconnected-(J2D-DP1_M2C_N-PadA3)") (class "Default")
      (node (ref "J2") (pin "A3") (pinfunction "DP1_M2C_N_A3") (pintype "passive+no_connect"))
    )
    (net (code "182") (name "unconnected-(J2D-DP1_M2C_P-PadA2)") (class "Default")
      (node (ref "J2") (pin "A2") (pinfunction "DP1_M2C_P_A2") (pintype "passive+no_connect"))
    )
    (net (code "183") (name "unconnected-(J2D-DP2_C2M_N-PadA27)") (class "Default")
      (node (ref "J2") (pin "A27") (pinfunction "DP2_C2M_N_A27") (pintype "passive+no_connect"))
    )
    (net (code "184") (name "unconnected-(J2D-DP2_C2M_P-PadA26)") (class "Default")
      (node (ref "J2") (pin "A26") (pinfunction "DP2_C2M_P_A26") (pintype "passive+no_connect"))
    )
    (net (code "185") (name "unconnected-(J2D-DP2_M2C_N-PadA7)") (class "Default")
      (node (ref "J2") (pin "A7") (pinfunction "DP2_M2C_N_A7") (pintype "passive+no_connect"))
    )
    (net (code "186") (name "unconnected-(J2D-DP2_M2C_P-PadA6)") (class "Default")
      (node (ref "J2") (pin "A6") (pinfunction "DP2_M2C_P_A6") (pintype "passive+no_connect"))
    )
    (net (code "187") (name "unconnected-(J2D-DP3_C2M_N-PadA31)") (class "Default")
      (node (ref "J2") (pin "A31") (pinfunction "DP3_C2M_N_A31") (pintype "passive+no_connect"))
    )
    (net (code "188") (name "unconnected-(J2D-DP3_C2M_P-PadA30)") (class "Default")
      (node (ref "J2") (pin "A30") (pinfunction "DP3_C2M_P_A30") (pintype "passive+no_connect"))
    )
    (net (code "189") (name "unconnected-(J2D-DP3_M2C_N-PadA11)") (class "Default")
      (node (ref "J2") (pin "A11") (pinfunction "DP3_M2C_N_A11") (pintype "passive+no_connect"))
    )
    (net (code "190") (name "unconnected-(J2D-DP3_M2C_P-PadA10)") (class "Default")
      (node (ref "J2") (pin "A10") (pinfunction "DP3_M2C_P_A10") (pintype "passive+no_connect"))
    )
    (net (code "191") (name "unconnected-(J2D-DP4_C2M_N-PadA35)") (class "Default")
      (node (ref "J2") (pin "A35") (pinfunction "DP4_C2M_N_A35") (pintype "passive+no_connect"))
    )
    (net (code "192") (name "unconnected-(J2D-DP4_C2M_P-PadA34)") (class "Default")
      (node (ref "J2") (pin "A34") (pinfunction "DP4_C2M_P_A34") (pintype "passive+no_connect"))
    )
    (net (code "193") (name "unconnected-(J2D-DP4_M2C_N-PadA15)") (class "Default")
      (node (ref "J2") (pin "A15") (pinfunction "DP4_M2C_N_A15") (pintype "passive+no_connect"))
    )
    (net (code "194") (name "unconnected-(J2D-DP4_M2C_P-PadA14)") (class "Default")
      (node (ref "J2") (pin "A14") (pinfunction "DP4_M2C_P_A14") (pintype "passive+no_connect"))
    )
    (net (code "195") (name "unconnected-(J2D-DP5_C2M_N-PadA39)") (class "Default")
      (node (ref "J2") (pin "A39") (pinfunction "DP5_C2M_N_A39") (pintype "passive+no_connect"))
    )
    (net (code "196") (name "unconnected-(J2D-DP5_C2M_P-PadA38)") (class "Default")
      (node (ref "J2") (pin "A38") (pinfunction "DP5_C2M_P_A38") (pintype "passive+no_connect"))
    )
    (net (code "197") (name "unconnected-(J2D-DP5_M2C_N-PadA19)") (class "Default")
      (node (ref "J2") (pin "A19") (pinfunction "DP5_M2C_N_A19") (pintype "passive+no_connect"))
    )
    (net (code "198") (name "unconnected-(J2D-DP5_M2C_P-PadA18)") (class "Default")
      (node (ref "J2") (pin "A18") (pinfunction "DP5_M2C_P_A18") (pintype "passive+no_connect"))
    )
    (net (code "199") (name "unconnected-(J2D-DP6_C2M_N-PadB37)") (class "Default")
      (node (ref "J2") (pin "B37") (pinfunction "DP6_C2M_N_B37") (pintype "passive+no_connect"))
    )
    (net (code "200") (name "unconnected-(J2D-DP6_C2M_P-PadB36)") (class "Default")
      (node (ref "J2") (pin "B36") (pinfunction "DP6_C2M_P_B36") (pintype "passive+no_connect"))
    )
    (net (code "201") (name "unconnected-(J2D-DP6_M2C_N-PadB17)") (class "Default")
      (node (ref "J2") (pin "B17") (pinfunction "DP6_M2C_N_B17") (pintype "passive+no_connect"))
    )
    (net (code "202") (name "unconnected-(J2D-DP6_M2C_P-PadB16)") (class "Default")
      (node (ref "J2") (pin "B16") (pinfunction "DP6_M2C_P_B16") (pintype "passive+no_connect"))
    )
    (net (code "203") (name "unconnected-(J2D-DP7_C2M_N-PadB33)") (class "Default")
      (node (ref "J2") (pin "B33") (pinfunction "DP7_C2M_N_B33") (pintype "passive+no_connect"))
    )
    (net (code "204") (name "unconnected-(J2D-DP7_C2M_P-PadB32)") (class "Default")
      (node (ref "J2") (pin "B32") (pinfunction "DP7_C2M_P_B32") (pintype "passive+no_connect"))
    )
    (net (code "205") (name "unconnected-(J2D-DP7_M2C_N-PadB13)") (class "Default")
      (node (ref "J2") (pin "B13") (pinfunction "DP7_M2C_N_B13") (pintype "passive+no_connect"))
    )
    (net (code "206") (name "unconnected-(J2D-DP7_M2C_P-PadB12)") (class "Default")
      (node (ref "J2") (pin "B12") (pinfunction "DP7_M2C_P_B12") (pintype "passive+no_connect"))
    )
    (net (code "207") (name "unconnected-(J2D-DP8_C2M_N-PadB29)") (class "Default")
      (node (ref "J2") (pin "B29") (pinfunction "DP8_C2M_N_B29") (pintype "passive+no_connect"))
    )
    (net (code "208") (name "unconnected-(J2D-DP8_C2M_P-PadB28)") (class "Default")
      (node (ref "J2") (pin "B28") (pinfunction "DP8_C2M_P_B28") (pintype "passive+no_connect"))
    )
    (net (code "209") (name "unconnected-(J2D-DP8_M2C_N-PadB9)") (class "Default")
      (node (ref "J2") (pin "B9") (pinfunction "DP8_M2C_N_B9") (pintype "passive+no_connect"))
    )
    (net (code "210") (name "unconnected-(J2D-DP8_M2C_P-PadB8)") (class "Default")
      (node (ref "J2") (pin "B8") (pinfunction "DP8_M2C_P_B8") (pintype "passive+no_connect"))
    )
    (net (code "211") (name "unconnected-(J2D-DP9_C2M_N-PadB25)") (class "Default")
      (node (ref "J2") (pin "B25") (pinfunction "DP9_C2M_N_B25") (pintype "passive+no_connect"))
    )
    (net (code "212") (name "unconnected-(J2D-DP9_C2M_P-PadB24)") (class "Default")
      (node (ref "J2") (pin "B24") (pinfunction "DP9_C2M_P_B24") (pintype "passive+no_connect"))
    )
    (net (code "213") (name "unconnected-(J2D-DP9_M2C_N-PadB5)") (class "Default")
      (node (ref "J2") (pin "B5") (pinfunction "DP9_M2C_N_B5") (pintype "passive+no_connect"))
    )
    (net (code "214") (name "unconnected-(J2D-DP9_M2C_P-PadB4)") (class "Default")
      (node (ref "J2") (pin "B4") (pinfunction "DP9_M2C_P_B4") (pintype "passive+no_connect"))
    )
    (net (code "215") (name "unconnected-(J2E-CLK0_C2M_N-PadG3)") (class "Default")
      (node (ref "J2") (pin "G3") (pinfunction "CLK0_C2M_N_G3") (pintype "passive+no_connect"))
    )
    (net (code "216") (name "unconnected-(J2E-CLK0_C2M_P-PadG2)") (class "Default")
      (node (ref "J2") (pin "G2") (pinfunction "CLK0_C2M_P_G2") (pintype "passive+no_connect"))
    )
    (net (code "217") (name "unconnected-(J2E-CLK0_M2C_N-PadH5)") (class "Default")
      (node (ref "J2") (pin "H5") (pinfunction "CLK0_M2C_N_H5") (pintype "passive+no_connect"))
    )
    (net (code "218") (name "unconnected-(J2E-CLK0_M2C_P-PadH4)") (class "Default")
      (node (ref "J2") (pin "H4") (pinfunction "CLK0_M2C_P_H4") (pintype "passive+no_connect"))
    )
    (net (code "219") (name "unconnected-(J2E-CLK1_C2M_N-PadJ3)") (class "Default")
      (node (ref "J2") (pin "J3") (pinfunction "CLK1_C2M_N_J3") (pintype "passive+no_connect"))
    )
    (net (code "220") (name "unconnected-(J2E-CLK1_C2M_P-PadJ2)") (class "Default")
      (node (ref "J2") (pin "J2") (pinfunction "CLK1_C2M_P_J2") (pintype "passive+no_connect"))
    )
    (net (code "221") (name "unconnected-(J2E-CLK1_M2C_N-PadK5)") (class "Default")
      (node (ref "J2") (pin "K5") (pinfunction "CLK1_M2C_N_K5") (pintype "passive+no_connect"))
    )
    (net (code "222") (name "unconnected-(J2E-CLK1_M2C_P-PadK4)") (class "Default")
      (node (ref "J2") (pin "K4") (pinfunction "CLK1_M2C_P_K4") (pintype "passive+no_connect"))
    )
    (net (code "223") (name "unconnected-(J2E-GBTCLK1_M2C_N-PadB21)") (class "Default")
      (node (ref "J2") (pin "B21") (pinfunction "GBTCLK1_M2C_N_B21") (pintype "passive+no_connect"))
    )
    (net (code "224") (name "unconnected-(J2E-GBTCLK1_M2C_P-PadB20)") (class "Default")
      (node (ref "J2") (pin "B20") (pinfunction "GBTCLK1_M2C_P_B20") (pintype "passive+no_connect"))
    )
    (net (code "225") (name "unconnected-(J2E-PG_C2M-PadD1)") (class "Default")
      (node (ref "J2") (pin "D1") (pinfunction "PG_C2M_D1") (pintype "passive+no_connect"))
    )
    (net (code "226") (name "unconnected-(J2E-PG_M2C-PadF1)") (class "Default")
      (node (ref "J2") (pin "F1") (pinfunction "PG_M2C_F1") (pintype "passive+no_connect"))
    )
    (net (code "227") (name "unconnected-(J2E-RES0-PadB40)") (class "Default")
      (node (ref "J2") (pin "B40") (pinfunction "RES0_B40") (pintype "passive+no_connect"))
    )
    (net (code "228") (name "unconnected-(J2E-RES1-PadB1)") (class "Default")
      (node (ref "J2") (pin "B1") (pinfunction "RES1_B1") (pintype "passive+no_connect"))
    )
    (net (code "229") (name "unconnected-(J2E-TCK-PadD29)") (class "Default")
      (node (ref "J2") (pin "D29") (pinfunction "TCK_D29") (pintype "passive+no_connect"))
    )
    (net (code "230") (name "unconnected-(J2E-TMS-PadD33)") (class "Default")
      (node (ref "J2") (pin "D33") (pinfunction "TMS_D33") (pintype "passive+no_connect"))
    )
    (net (code "231") (name "unconnected-(J2E-TRST_L-PadD34)") (class "Default")
      (node (ref "J2") (pin "D34") (pinfunction "TRST_L_D34") (pintype "passive+no_connect"))
    )
    (net (code "232") (name "unconnected-(J2F-VIO_B_M2C-PadJ39)") (class "Default")
      (node (ref "J2") (pin "J39") (pinfunction "VIO_B_M2C_J39") (pintype "passive+no_connect"))
    )
    (net (code "233") (name "unconnected-(J2F-VIO_B_M2C-PadK40)") (class "Default")
      (node (ref "J2") (pin "K40") (pinfunction "VIO_B_M2C_K40") (pintype "passive+no_connect"))
    )
    (net (code "234") (name "unconnected-(J2F-VREF_A_M2C-PadH1)") (class "Default")
      (node (ref "J2") (pin "H1") (pinfunction "VREF_A_M2C_H1") (pintype "passive+no_connect"))
    )
    (net (code "235") (name "unconnected-(J2F-VREF_B_M2C-PadK1)") (class "Default")
      (node (ref "J2") (pin "K1") (pinfunction "VREF_B_M2C_K1") (pintype "passive+no_connect"))
    )
  )
)
